# Sheet1.net
KiCad netlist of a schematic drawn in Altium Designer
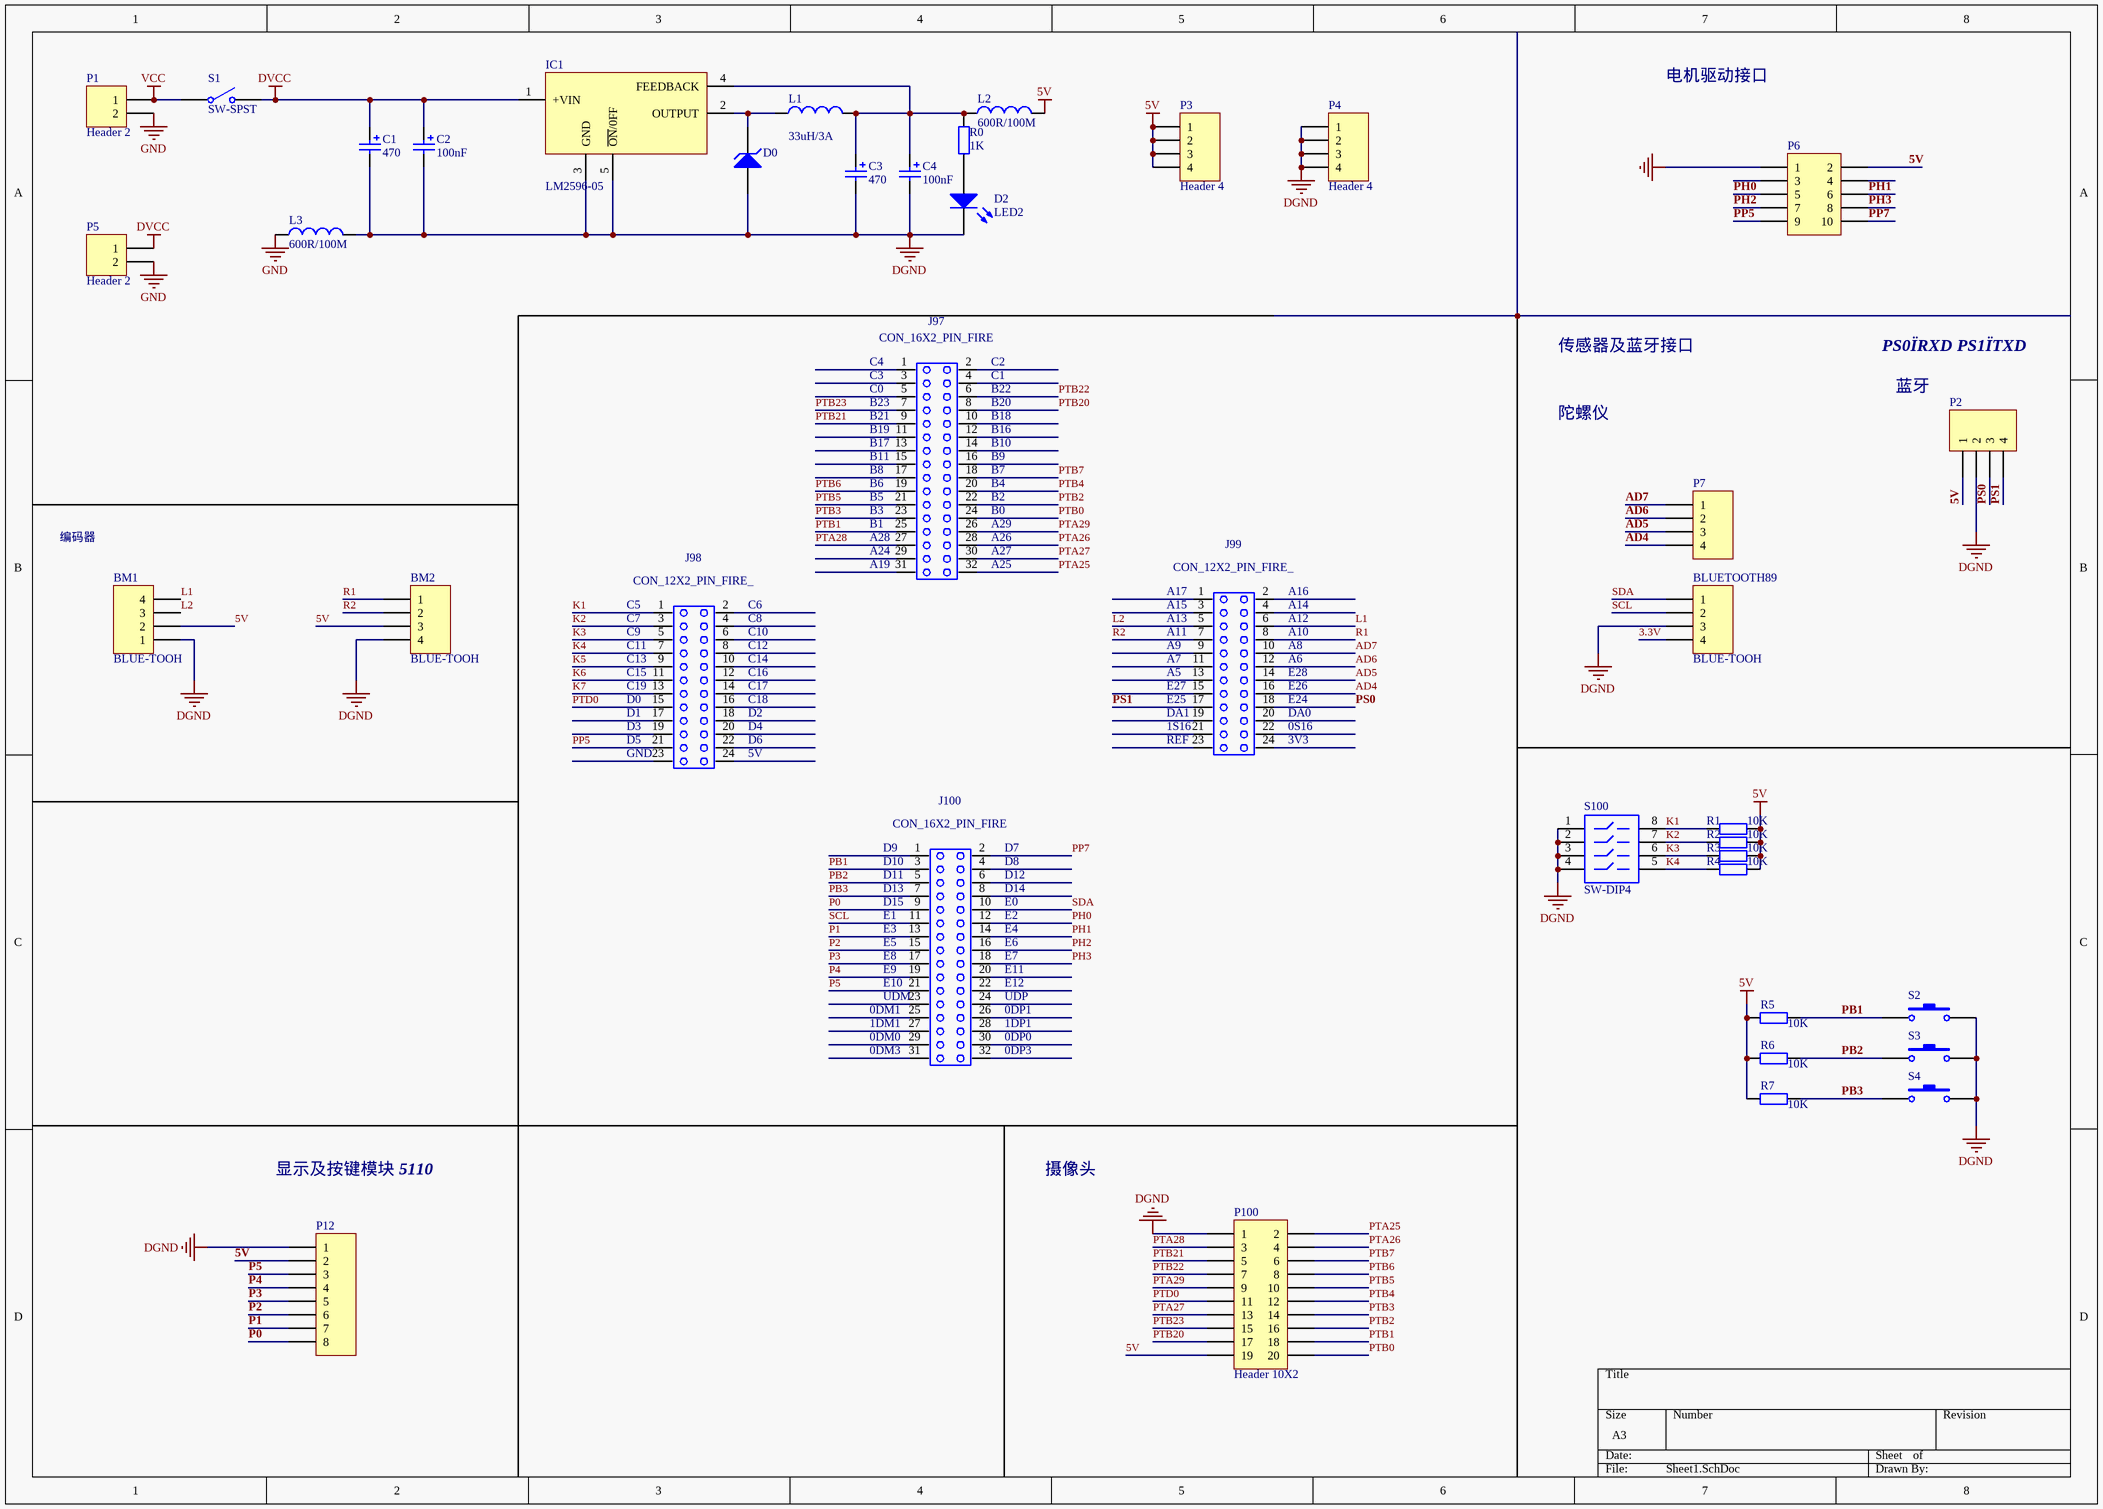
[diagram p0: Sheet1.SchDoc]

(export (version "E")
  (design (tool "Eeschema 10.0.6"))
  (components
    (comp (ref "BLUETOOTH89")
      (value "BLUE-TOOH")
      (footprint "HDR1X4")
      (description "Header, 4-Pin")
      (fields (field (name "PUBLISHER") "Altium Limited"))
      (libsource (lib "Miscellaneous Connectors") (part "Header 4"))
    )
    (comp (ref "BM1")
      (value "BLUE-TOOH")
      (footprint "HDR1X4")
      (description "Header, 4-Pin")
      (fields (field (name "PUBLISHER") "Altium Limited"))
      (libsource (lib "") (part "Header 4_2"))
    )
    (comp (ref "BM2")
      (value "BLUE-TOOH")
      (footprint "HDR1X4")
      (description "Header, 4-Pin")
      (fields (field (name "PUBLISHER") "Altium Limited"))
      (libsource (lib "Miscellaneous Connectors") (part "Header 4"))
    )
    (comp (ref "C1")
      (value "470")
      (footprint "ccc")
      (description "Polarized Capacitor (Axial)")
      (fields (field (name "PUBLISHER") "Altium Limited"))
      (libsource (lib "Miscellaneous Devices") (part "Cap Pol2"))
    )
    (comp (ref "C2")
      (value "100nF")
      (footprint "C0805")
      (description "Polarized Capacitor (Axial)")
      (fields (field (name "PUBLISHER") "Altium Limited"))
      (libsource (lib "Miscellaneous Devices") (part "Cap Pol2"))
    )
    (comp (ref "C3")
      (value "470")
      (footprint "ccc")
      (description "Polarized Capacitor (Axial)")
      (fields (field (name "PUBLISHER") "Altium Limited"))
      (libsource (lib "Miscellaneous Devices") (part "Cap Pol2"))
    )
    (comp (ref "C4")
      (value "100nF")
      (footprint "C0805")
      (description "Polarized Capacitor (Axial)")
      (fields (field (name "PUBLISHER") "Altium Limited"))
      (libsource (lib "Miscellaneous Devices") (part "Cap Pol2"))
    )
    (comp (ref "D0")
      (value "D Zener")
      (footprint "D1810")
      (description "Zener Diode")
      (fields (field (name "PUBLISHER") "Altium Limited"))
      (libsource (lib "Miscellaneous Devices") (part "D Zener"))
    )
    (comp (ref "D2")
      (value "LED2")
      (footprint "D0805")
      (description "Typical RED, GREEN, YELLOW, AMBER GaAs LED")
      (fields (field (name "PUBLISHER") "Altium Limited"))
      (libsource (lib "Miscellaneous Devices") (part "LED2"))
    )
    (comp (ref "IC1")
      (value "LM2596-05")
      (footprint "TO-263-5")
      (libsource (lib "飞思卡尔元件库") (part "LM2596-05"))
    )
    (comp (ref "J97")
      (value "CON_16X2_PIN_FIRE")
      (footprint "CON-16X2-2.54")
      (description "16X2,pin,2.54mm")
      (libsource (lib "*") (part "CON_16X2_PIN_FIRE"))
    )
    (comp (ref "J98")
      (value "CON_12X2_PIN_FIRE_")
      (footprint "CON-12X2-2.54")
      (description "12X2,pin,2.54mm")
      (libsource (lib "*") (part "CON_12X2_PIN_FIRE_"))
    )
    (comp (ref "J99")
      (value "CON_12X2_PIN_FIRE_")
      (footprint "CON-12X2-2.54")
      (description "12X2,pin,2.54mm")
      (libsource (lib "*") (part "CON_12X2_PIN_FIRE_"))
    )
    (comp (ref "J100")
      (value "CON_16X2_PIN_FIRE")
      (footprint "CON-16X2-2.54")
      (description "16X2,pin,2.54mm")
      (libsource (lib "*") (part "CON_16X2_PIN_FIRE"))
    )
    (comp (ref "L1")
      (value "33uH/3A")
      (footprint "L-12*12MM-S")
      (description "Inductor")
      (fields (field (name "PUBLISHER") "Altium Limited"))
      (libsource (lib "Miscellaneous Devices") (part "Inductor"))
    )
    (comp (ref "L2")
      (value "600R/100M")
      (footprint "L1206")
      (description "Inductor")
      (fields (field (name "PUBLISHER") "Altium Limited"))
      (libsource (lib "Miscellaneous Devices") (part "Inductor"))
    )
    (comp (ref "L3")
      (value "600R/100M")
      (footprint "L1206")
      (description "Inductor")
      (fields (field (name "PUBLISHER") "Altium Limited"))
      (libsource (lib "Miscellaneous Devices") (part "Inductor"))
    )
    (comp (ref "P1")
      (value "Header 2")
      (footprint "SIP2-1")
      (description "Header, 2-Pin")
      (fields (field (name "PUBLISHER") "Altium Limited"))
      (libsource (lib "Miscellaneous Connectors") (part "Header 2"))
    )
    (comp (ref "P2")
      (value "Header 4")
      (footprint "HDR1X4")
      (description "Header, 4-Pin")
      (fields (field (name "PUBLISHER") "Altium Limited"))
      (libsource (lib "") (part "Header 4_1"))
    )
    (comp (ref "P3")
      (value "Header 4")
      (footprint "HDR1X4")
      (description "Header, 4-Pin")
      (fields (field (name "PUBLISHER") "Altium Limited"))
      (libsource (lib "Miscellaneous Connectors") (part "Header 4"))
    )
    (comp (ref "P4")
      (value "Header 4")
      (footprint "HDR1X4")
      (description "Header, 4-Pin")
      (fields (field (name "PUBLISHER") "Altium Limited"))
      (libsource (lib "Miscellaneous Connectors") (part "Header 4"))
    )
    (comp (ref "P5")
      (value "Header 2")
      (footprint "SIP2-1")
      (description "Header, 2-Pin")
      (fields (field (name "PUBLISHER") "Altium Limited"))
      (libsource (lib "Miscellaneous Connectors") (part "Header 2"))
    )
    (comp (ref "P6")
      (value "Header 5X2")
      (footprint "HDR2X5")
      (description "Header, 5-Pin, Dual row")
      (fields (field (name "PUBLISHER") "Altium Limited"))
      (libsource (lib "Miscellaneous Connectors") (part "Header 5X2"))
    )
    (comp (ref "P7")
      (value "Header 4")
      (footprint "HDR1X4")
      (description "Header, 4-Pin")
      (fields (field (name "PUBLISHER") "Altium Limited"))
      (libsource (lib "Miscellaneous Connectors") (part "Header 4"))
    )
    (comp (ref "P12")
      (value "Header 8")
      (footprint "HDR1X8")
      (description "Header, 8-Pin")
      (fields (field (name "PUBLISHER") "Altium Limited"))
      (libsource (lib "Miscellaneous Connectors") (part "Header 8"))
    )
    (comp (ref "P100")
      (value "Header 10X2")
      (footprint "HDR2X10")
      (description "Header, 10-Pin, Dual row")
      (fields (field (name "PUBLISHER") "Altium Limited"))
      (libsource (lib "Miscellaneous Connectors") (part "Header 10X2"))
    )
    (comp (ref "R0")
      (value "1K")
      (footprint "R0805")
      (description "Resistor")
      (fields (field (name "Comment") "Res2") (field (name "PUBLISHER") "Altium Limited"))
      (libsource (lib "") (part "Res2_1"))
    )
    (comp (ref "R1")
      (value "10K")
      (footprint "AXIAL-0.4")
      (description "Resistor")
      (fields (field (name "Comment") "Res2") (field (name "PUBLISHER") "Altium Limited"))
      (libsource (lib "Miscellaneous Devices") (part "Res2"))
    )
    (comp (ref "R2")
      (value "10K")
      (footprint "AXIAL-0.4")
      (description "Resistor")
      (fields (field (name "Comment") "Res2") (field (name "PUBLISHER") "Altium Limited"))
      (libsource (lib "Miscellaneous Devices") (part "Res2"))
    )
    (comp (ref "R3")
      (value "10K")
      (footprint "AXIAL-0.4")
      (description "Resistor")
      (fields (field (name "Comment") "Res2") (field (name "PUBLISHER") "Altium Limited"))
      (libsource (lib "Miscellaneous Devices") (part "Res2"))
    )
    (comp (ref "R4")
      (value "10K")
      (footprint "AXIAL-0.4")
      (description "Resistor")
      (fields (field (name "Comment") "Res2") (field (name "PUBLISHER") "Altium Limited"))
      (libsource (lib "Miscellaneous Devices") (part "Res2"))
    )
    (comp (ref "R5")
      (value "10K")
      (footprint "AXIAL-0.4")
      (description "Resistor")
      (fields (field (name "Comment") "Res2") (field (name "PUBLISHER") "Altium Limited"))
      (libsource (lib "Miscellaneous Devices") (part "Res2"))
    )
    (comp (ref "R6")
      (value "10K")
      (footprint "AXIAL-0.4")
      (description "Resistor")
      (fields (field (name "Comment") "Res2") (field (name "PUBLISHER") "Altium Limited"))
      (libsource (lib "Miscellaneous Devices") (part "Res2"))
    )
    (comp (ref "R7")
      (value "10K")
      (footprint "AXIAL-0.4")
      (description "Resistor")
      (fields (field (name "Comment") "Res2") (field (name "PUBLISHER") "Altium Limited"))
      (libsource (lib "Miscellaneous Devices") (part "Res2"))
    )
    (comp (ref "S1")
      (value "SW-SPST")
      (footprint "PCBComponent_1")
      (description "Single-Pole, Single-Throw Switch")
      (fields (field (name "PUBLISHER") "Altium Limited"))
      (libsource (lib "Miscellaneous Devices") (part "SW-SPST"))
    )
    (comp (ref "S2")
      (value "SW-PB")
      (footprint "白色按键")
      (description "Switch")
      (fields (field (name "PUBLISHER") "Altium Limited"))
      (libsource (lib "Miscellaneous Devices") (part "SW-PB"))
    )
    (comp (ref "S3")
      (value "SW-PB")
      (footprint "白色按键")
      (description "Switch")
      (fields (field (name "PUBLISHER") "Altium Limited"))
      (libsource (lib "Miscellaneous Devices") (part "SW-PB"))
    )
    (comp (ref "S4")
      (value "SW-PB")
      (footprint "白色按键")
      (description "Switch")
      (fields (field (name "PUBLISHER") "Altium Limited"))
      (libsource (lib "Miscellaneous Devices") (part "SW-PB"))
    )
    (comp (ref "S100")
      (value "SW-DIP4")
      (footprint "DIP-8")
      (description "DIP Switch")
      (fields (field (name "PUBLISHER") "Altium Limited"))
      (libsource (lib "Miscellaneous Devices") (part "SW-DIP4"))
    )
  )
  (nets
    (net (code "1") (name "/3.3V") (class "Default")
      (node (ref "BLUETOOTH89") (pin "4") (pinfunction "4_4") (pintype "passive"))
    )
    (net (code "2") (name "/AD4") (class "Default")
      (node (ref "J99") (pin "16") (pintype "passive"))
      (node (ref "P7") (pin "4") (pinfunction "4_4") (pintype "passive"))
    )
    (net (code "3") (name "/AD5") (class "Default")
      (node (ref "J99") (pin "14") (pintype "passive"))
      (node (ref "P7") (pin "3") (pinfunction "3_3") (pintype "passive"))
    )
    (net (code "4") (name "/AD6") (class "Default")
      (node (ref "J99") (pin "12") (pintype "passive"))
      (node (ref "P7") (pin "2") (pinfunction "2_2") (pintype "passive"))
    )
    (net (code "5") (name "/AD7") (class "Default")
      (node (ref "J99") (pin "10") (pintype "passive"))
      (node (ref "P7") (pin "1") (pinfunction "1_1") (pintype "passive"))
    )
    (net (code "6") (name "/K1") (class "Default")
      (node (ref "J98") (pin "1") (pintype "passive"))
      (node (ref "R1") (pin "1") (pinfunction "1_1") (pintype "passive"))
      (node (ref "S100") (pin "8") (pinfunction "8_8") (pintype "passive"))
    )
    (net (code "7") (name "/K2") (class "Default")
      (node (ref "J98") (pin "3") (pintype "passive"))
      (node (ref "R2") (pin "1") (pinfunction "1_1") (pintype "passive"))
      (node (ref "S100") (pin "7") (pinfunction "7_7") (pintype "passive"))
    )
    (net (code "8") (name "/K3") (class "Default")
      (node (ref "J98") (pin "5") (pintype "passive"))
      (node (ref "R3") (pin "1") (pinfunction "1_1") (pintype "passive"))
      (node (ref "S100") (pin "6") (pinfunction "6_6") (pintype "passive"))
    )
    (net (code "9") (name "/K4") (class "Default")
      (node (ref "J98") (pin "7") (pintype "passive"))
      (node (ref "R4") (pin "1") (pinfunction "1_1") (pintype "passive"))
      (node (ref "S100") (pin "5") (pinfunction "5_5") (pintype "passive"))
    )
    (net (code "10") (name "/K5") (class "Default") (node (ref "J98") (pin "9") (pintype "passive")))
    (net (code "11") (name "/K6") (class "Default") (node (ref "J98") (pin "11") (pintype "passive")))
    (net (code "12") (name "/K7") (class "Default") (node (ref "J98") (pin "13") (pintype "passive")))
    (net (code "13") (name "/L1") (class "Default")
      (node (ref "BM1") (pin "4") (pinfunction "4_4") (pintype "passive"))
      (node (ref "J99") (pin "6") (pintype "passive"))
    )
    (net (code "14") (name "/L2") (class "Default")
      (node (ref "BM1") (pin "3") (pinfunction "3_3") (pintype "passive"))
      (node (ref "J99") (pin "5") (pintype "passive"))
    )
    (net (code "15") (name "/P0") (class "Default")
      (node (ref "J100") (pin "9") (pintype "passive"))
      (node (ref "P12") (pin "8") (pinfunction "8_8") (pintype "passive"))
    )
    (net (code "16") (name "/P1") (class "Default")
      (node (ref "J100") (pin "13") (pintype "passive"))
      (node (ref "P12") (pin "7") (pinfunction "7_7") (pintype "passive"))
    )
    (net (code "17") (name "/P2") (class "Default")
      (node (ref "J100") (pin "15") (pintype "passive"))
      (node (ref "P12") (pin "6") (pinfunction "6_6") (pintype "passive"))
    )
    (net (code "18") (name "/P3") (class "Default")
      (node (ref "J100") (pin "17") (pintype "passive"))
      (node (ref "P12") (pin "5") (pinfunction "5_5") (pintype "passive"))
    )
    (net (code "19") (name "/P4") (class "Default")
      (node (ref "J100") (pin "19") (pintype "passive"))
      (node (ref "P12") (pin "4") (pinfunction "4_4") (pintype "passive"))
    )
    (net (code "20") (name "/P5") (class "Default")
      (node (ref "J100") (pin "21") (pintype "passive"))
      (node (ref "P12") (pin "3") (pinfunction "3_3") (pintype "passive"))
    )
    (net (code "21") (name "/PB1") (class "Default")
      (node (ref "J100") (pin "3") (pintype "passive"))
      (node (ref "R5") (pin "2") (pinfunction "2_2") (pintype "passive"))
      (node (ref "S2") (pin "1") (pinfunction "1_1") (pintype "passive"))
    )
    (net (code "22") (name "/PB2") (class "Default")
      (node (ref "J100") (pin "5") (pintype "passive"))
      (node (ref "R6") (pin "2") (pinfunction "2_2") (pintype "passive"))
      (node (ref "S3") (pin "1") (pinfunction "1_1") (pintype "passive"))
    )
    (net (code "23") (name "/PB3") (class "Default")
      (node (ref "J100") (pin "7") (pintype "passive"))
      (node (ref "R7") (pin "2") (pinfunction "2_2") (pintype "passive"))
      (node (ref "S4") (pin "1") (pinfunction "1_1") (pintype "passive"))
    )
    (net (code "24") (name "/PH0") (class "Default")
      (node (ref "J100") (pin "12") (pintype "passive"))
      (node (ref "P6") (pin "5") (pinfunction "5_5") (pintype "passive"))
    )
    (net (code "25") (name "/PH1") (class "Default")
      (node (ref "J100") (pin "14") (pintype "passive"))
      (node (ref "P6") (pin "6") (pinfunction "6_6") (pintype "passive"))
    )
    (net (code "26") (name "/PH2") (class "Default")
      (node (ref "J100") (pin "16") (pintype "passive"))
      (node (ref "P6") (pin "7") (pinfunction "7_7") (pintype "passive"))
    )
    (net (code "27") (name "/PH3") (class "Default")
      (node (ref "J100") (pin "18") (pintype "passive"))
      (node (ref "P6") (pin "8") (pinfunction "8_8") (pintype "passive"))
    )
    (net (code "28") (name "/PP5") (class "Default")
      (node (ref "J98") (pin "21") (pintype "passive"))
      (node (ref "P6") (pin "9") (pinfunction "9_9") (pintype "passive"))
    )
    (net (code "29") (name "/PP7") (class "Default")
      (node (ref "J100") (pin "2") (pintype "passive"))
      (node (ref "P6") (pin "10") (pinfunction "10_10") (pintype "passive"))
    )
    (net (code "30") (name "/PS0") (class "Default")
      (node (ref "J99") (pin "18") (pintype "passive"))
      (node (ref "P2") (pin "3") (pinfunction "3_3") (pintype "passive"))
    )
    (net (code "31") (name "/PS1") (class "Default")
      (node (ref "J99") (pin "17") (pintype "passive"))
      (node (ref "P2") (pin "4") (pinfunction "4_4") (pintype "passive"))
    )
    (net (code "32") (name "/PTA25") (class "Default")
      (node (ref "J97") (pin "32") (pintype "passive"))
      (node (ref "P100") (pin "2") (pinfunction "2_2") (pintype "passive"))
    )
    (net (code "33") (name "/PTA26") (class "Default")
      (node (ref "J97") (pin "28") (pintype "passive"))
      (node (ref "P100") (pin "4") (pinfunction "4_4") (pintype "passive"))
    )
    (net (code "34") (name "/PTA27") (class "Default")
      (node (ref "J97") (pin "30") (pintype "passive"))
      (node (ref "P100") (pin "13") (pinfunction "13_13") (pintype "passive"))
    )
    (net (code "35") (name "/PTA28") (class "Default")
      (node (ref "J97") (pin "27") (pintype "passive"))
      (node (ref "P100") (pin "3") (pinfunction "3_3") (pintype "passive"))
    )
    (net (code "36") (name "/PTA29") (class "Default")
      (node (ref "J97") (pin "26") (pintype "passive"))
      (node (ref "P100") (pin "9") (pinfunction "9_9") (pintype "passive"))
    )
    (net (code "37") (name "/PTB0") (class "Default")
      (node (ref "J97") (pin "24") (pintype "passive"))
      (node (ref "P100") (pin "20") (pinfunction "20_20") (pintype "passive"))
    )
    (net (code "38") (name "/PTB1") (class "Default")
      (node (ref "J97") (pin "25") (pintype "passive"))
      (node (ref "P100") (pin "18") (pinfunction "18_18") (pintype "passive"))
    )
    (net (code "39") (name "/PTB2") (class "Default")
      (node (ref "J97") (pin "22") (pintype "passive"))
      (node (ref "P100") (pin "16") (pinfunction "16_16") (pintype "passive"))
    )
    (net (code "40") (name "/PTB3") (class "Default")
      (node (ref "J97") (pin "23") (pintype "passive"))
      (node (ref "P100") (pin "14") (pinfunction "14_14") (pintype "passive"))
    )
    (net (code "41") (name "/PTB4") (class "Default")
      (node (ref "J97") (pin "20") (pintype "passive"))
      (node (ref "P100") (pin "12") (pinfunction "12_12") (pintype "passive"))
    )
    (net (code "42") (name "/PTB5") (class "Default")
      (node (ref "J97") (pin "21") (pintype "passive"))
      (node (ref "P100") (pin "10") (pinfunction "10_10") (pintype "passive"))
    )
    (net (code "43") (name "/PTB6") (class "Default")
      (node (ref "J97") (pin "19") (pintype "passive"))
      (node (ref "P100") (pin "8") (pinfunction "8_8") (pintype "passive"))
    )
    (net (code "44") (name "/PTB7") (class "Default")
      (node (ref "J97") (pin "18") (pintype "passive"))
      (node (ref "P100") (pin "6") (pinfunction "6_6") (pintype "passive"))
    )
    (net (code "45") (name "/PTB20") (class "Default")
      (node (ref "J97") (pin "8") (pintype "passive"))
      (node (ref "P100") (pin "17") (pinfunction "17_17") (pintype "passive"))
    )
    (net (code "46") (name "/PTB21") (class "Default")
      (node (ref "J97") (pin "9") (pintype "passive"))
      (node (ref "P100") (pin "5") (pinfunction "5_5") (pintype "passive"))
    )
    (net (code "47") (name "/PTB22") (class "Default")
      (node (ref "J97") (pin "6") (pintype "passive"))
      (node (ref "P100") (pin "7") (pinfunction "7_7") (pintype "passive"))
    )
    (net (code "48") (name "/PTB23") (class "Default")
      (node (ref "J97") (pin "7") (pintype "passive"))
      (node (ref "P100") (pin "15") (pinfunction "15_15") (pintype "passive"))
    )
    (net (code "49") (name "/PTD0") (class "Default")
      (node (ref "J98") (pin "15") (pintype "passive"))
      (node (ref "P100") (pin "11") (pinfunction "11_11") (pintype "passive"))
    )
    (net (code "50") (name "/R1") (class "Default")
      (node (ref "BM2") (pin "1") (pinfunction "1_1") (pintype "passive"))
      (node (ref "J99") (pin "8") (pintype "passive"))
    )
    (net (code "51") (name "/R2") (class "Default")
      (node (ref "BM2") (pin "2") (pinfunction "2_2") (pintype "passive"))
      (node (ref "J99") (pin "7") (pintype "passive"))
    )
    (net (code "52") (name "/SCL") (class "Default")
      (node (ref "BLUETOOTH89") (pin "2") (pinfunction "2_2") (pintype "passive"))
      (node (ref "J100") (pin "11") (pintype "passive"))
    )
    (net (code "53") (name "/SDA") (class "Default")
      (node (ref "BLUETOOTH89") (pin "1") (pinfunction "1_1") (pintype "passive"))
      (node (ref "J100") (pin "10") (pintype "passive"))
    )
    (net (code "54") (name "5V") (class "Default")
      (node (ref "BM1") (pin "2") (pinfunction "2_2") (pintype "passive"))
      (node (ref "BM2") (pin "3") (pinfunction "3_3") (pintype "passive"))
      (node (ref "L2") (pin "2") (pinfunction "2_2") (pintype "passive"))
      (node (ref "P100") (pin "19") (pinfunction "19_19") (pintype "passive"))
      (node (ref "P12") (pin "2") (pinfunction "2_2") (pintype "passive"))
      (node (ref "P2") (pin "1") (pinfunction "1_1") (pintype "passive"))
      (node (ref "P3") (pin "1") (pinfunction "1_1") (pintype "passive"))
      (node (ref "P3") (pin "2") (pinfunction "2_2") (pintype "passive"))
      (node (ref "P3") (pin "3") (pinfunction "3_3") (pintype "passive"))
      (node (ref "P3") (pin "4") (pinfunction "4_4") (pintype "passive"))
      (node (ref "P6") (pin "2") (pinfunction "2_2") (pintype "passive"))
      (node (ref "R1") (pin "2") (pinfunction "2_2") (pintype "passive"))
      (node (ref "R2") (pin "2") (pinfunction "2_2") (pintype "passive"))
      (node (ref "R3") (pin "2") (pinfunction "2_2") (pintype "passive"))
      (node (ref "R4") (pin "2") (pinfunction "2_2") (pintype "passive"))
      (node (ref "R5") (pin "1") (pinfunction "1_1") (pintype "passive"))
      (node (ref "R6") (pin "1") (pinfunction "1_1") (pintype "passive"))
      (node (ref "R7") (pin "1") (pinfunction "1_1") (pintype "passive"))
    )
    (net (code "55") (name "DGND") (class "Default")
      (node (ref "BLUETOOTH89") (pin "3") (pinfunction "3_3") (pintype "passive"))
      (node (ref "BM1") (pin "1") (pinfunction "1_1") (pintype "passive"))
      (node (ref "BM2") (pin "4") (pinfunction "4_4") (pintype "passive"))
      (node (ref "C1") (pin "2") (pinfunction "2_2") (pintype "passive"))
      (node (ref "C2") (pin "2") (pinfunction "2_2") (pintype "passive"))
      (node (ref "C3") (pin "2") (pinfunction "2_2") (pintype "passive"))
      (node (ref "C4") (pin "2") (pinfunction "2_2") (pintype "passive"))
      (node (ref "D0") (pin "1") (pinfunction "A_1") (pintype "passive"))
      (node (ref "D2") (pin "2") (pinfunction "K_2") (pintype "passive"))
      (node (ref "IC1") (pin "3") (pinfunction "GND_3") (pintype "passive"))
      (node (ref "IC1") (pin "5") (pinfunction "~{ON}/0FF_5") (pintype "passive"))
      (node (ref "L3") (pin "2") (pinfunction "2_2") (pintype "passive"))
      (node (ref "P100") (pin "1") (pinfunction "1_1") (pintype "passive"))
      (node (ref "P12") (pin "1") (pinfunction "1_1") (pintype "passive"))
      (node (ref "P2") (pin "2") (pinfunction "2_2") (pintype "passive"))
      (node (ref "P4") (pin "1") (pinfunction "1_1") (pintype "passive"))
      (node (ref "P4") (pin "2") (pinfunction "2_2") (pintype "passive"))
      (node (ref "P4") (pin "3") (pinfunction "3_3") (pintype "passive"))
      (node (ref "P4") (pin "4") (pinfunction "4_4") (pintype "passive"))
      (node (ref "S100") (pin "1") (pinfunction "1_1") (pintype "passive"))
      (node (ref "S100") (pin "2") (pinfunction "2_2") (pintype "passive"))
      (node (ref "S100") (pin "3") (pinfunction "3_3") (pintype "passive"))
      (node (ref "S100") (pin "4") (pinfunction "4_4") (pintype "passive"))
      (node (ref "S2") (pin "2") (pinfunction "2_2") (pintype "passive"))
      (node (ref "S3") (pin "2") (pinfunction "2_2") (pintype "passive"))
      (node (ref "S4") (pin "2") (pinfunction "2_2") (pintype "passive"))
    )
    (net (code "56") (name "DVCC") (class "Default")
      (node (ref "C1") (pin "1") (pinfunction "1_1") (pintype "passive"))
      (node (ref "C2") (pin "1") (pinfunction "1_1") (pintype "passive"))
      (node (ref "IC1") (pin "1") (pinfunction "+VIN_1") (pintype "passive"))
      (node (ref "P5") (pin "1") (pinfunction "1_1") (pintype "passive"))
      (node (ref "S1") (pin "2") (pinfunction "NO_2") (pintype "passive"))
    )
    (net (code "57") (name "GND") (class "Default")
      (node (ref "L3") (pin "1") (pinfunction "1_1") (pintype "passive"))
      (node (ref "P1") (pin "2") (pinfunction "2_2") (pintype "passive"))
      (node (ref "P5") (pin "2") (pinfunction "2_2") (pintype "passive"))
      (node (ref "P6") (pin "1") (pinfunction "1_1") (pintype "passive"))
    )
    (net (code "58") (name "Net-(D0-K)") (class "Default")
      (node (ref "D0") (pin "2") (pinfunction "K_2") (pintype "passive"))
      (node (ref "IC1") (pin "2") (pinfunction "OUTPUT_2") (pintype "passive"))
      (node (ref "L1") (pin "1") (pinfunction "1_1") (pintype "passive"))
    )
    (net (code "59") (name "Net-(D2-A)") (class "Default")
      (node (ref "D2") (pin "1") (pinfunction "A_1") (pintype "passive"))
      (node (ref "R0") (pin "2") (pinfunction "2_2") (pintype "passive"))
    )
    (net (code "60") (name "Net-(IC1-FEEDBACK)") (class "Default")
      (node (ref "C3") (pin "1") (pinfunction "1_1") (pintype "passive"))
      (node (ref "C4") (pin "1") (pinfunction "1_1") (pintype "passive"))
      (node (ref "IC1") (pin "4") (pinfunction "FEEDBACK_4") (pintype "passive"))
      (node (ref "L1") (pin "2") (pinfunction "2_2") (pintype "passive"))
      (node (ref "L2") (pin "1") (pinfunction "1_1") (pintype "passive"))
      (node (ref "R0") (pin "1") (pinfunction "1_1") (pintype "passive"))
    )
    (net (code "61") (name "VCC") (class "Default")
      (node (ref "P1") (pin "1") (pinfunction "1_1") (pintype "passive"))
      (node (ref "S1") (pin "1") (pinfunction "COMMON_1") (pintype "passive"))
    )
    (net (code "62") (name "unconnected-(J97-Pad1)") (class "Default")
      (node (ref "J97") (pin "1") (pintype "passive"))
    )
    (net (code "63") (name "unconnected-(J97-Pad2)") (class "Default")
      (node (ref "J97") (pin "2") (pintype "passive"))
    )
    (net (code "64") (name "unconnected-(J97-Pad3)") (class "Default")
      (node (ref "J97") (pin "3") (pintype "passive"))
    )
    (net (code "65") (name "unconnected-(J97-Pad4)") (class "Default")
      (node (ref "J97") (pin "4") (pintype "passive"))
    )
    (net (code "66") (name "unconnected-(J97-Pad5)") (class "Default")
      (node (ref "J97") (pin "5") (pintype "passive"))
    )
    (net (code "67") (name "unconnected-(J97-Pad10)") (class "Default")
      (node (ref "J97") (pin "10") (pintype "passive"))
    )
    (net (code "68") (name "unconnected-(J97-Pad11)") (class "Default")
      (node (ref "J97") (pin "11") (pintype "passive"))
    )
    (net (code "69") (name "unconnected-(J97-Pad12)") (class "Default")
      (node (ref "J97") (pin "12") (pintype "passive"))
    )
    (net (code "70") (name "unconnected-(J97-Pad13)") (class "Default")
      (node (ref "J97") (pin "13") (pintype "passive"))
    )
    (net (code "71") (name "unconnected-(J97-Pad14)") (class "Default")
      (node (ref "J97") (pin "14") (pintype "passive"))
    )
    (net (code "72") (name "unconnected-(J97-Pad15)") (class "Default")
      (node (ref "J97") (pin "15") (pintype "passive"))
    )
    (net (code "73") (name "unconnected-(J97-Pad16)") (class "Default")
      (node (ref "J97") (pin "16") (pintype "passive"))
    )
    (net (code "74") (name "unconnected-(J97-Pad17)") (class "Default")
      (node (ref "J97") (pin "17") (pintype "passive"))
    )
    (net (code "75") (name "unconnected-(J97-Pad29)") (class "Default")
      (node (ref "J97") (pin "29") (pintype "passive"))
    )
    (net (code "76") (name "unconnected-(J97-Pad31)") (class "Default")
      (node (ref "J97") (pin "31") (pintype "passive"))
    )
    (net (code "77") (name "unconnected-(J98-Pad2)") (class "Default")
      (node (ref "J98") (pin "2") (pintype "passive"))
    )
    (net (code "78") (name "unconnected-(J98-Pad4)") (class "Default")
      (node (ref "J98") (pin "4") (pintype "passive"))
    )
    (net (code "79") (name "unconnected-(J98-Pad6)") (class "Default")
      (node (ref "J98") (pin "6") (pintype "passive"))
    )
    (net (code "80") (name "unconnected-(J98-Pad8)") (class "Default")
      (node (ref "J98") (pin "8") (pintype "passive"))
    )
    (net (code "81") (name "unconnected-(J98-Pad10)") (class "Default")
      (node (ref "J98") (pin "10") (pintype "passive"))
    )
    (net (code "82") (name "unconnected-(J98-Pad12)") (class "Default")
      (node (ref "J98") (pin "12") (pintype "passive"))
    )
    (net (code "83") (name "unconnected-(J98-Pad14)") (class "Default")
      (node (ref "J98") (pin "14") (pintype "passive"))
    )
    (net (code "84") (name "unconnected-(J98-Pad16)") (class "Default")
      (node (ref "J98") (pin "16") (pintype "passive"))
    )
    (net (code "85") (name "unconnected-(J98-Pad17)") (class "Default")
      (node (ref "J98") (pin "17") (pintype "passive"))
    )
    (net (code "86") (name "unconnected-(J98-Pad18)") (class "Default")
      (node (ref "J98") (pin "18") (pintype "passive"))
    )
    (net (code "87") (name "unconnected-(J98-Pad19)") (class "Default")
      (node (ref "J98") (pin "19") (pintype "passive"))
    )
    (net (code "88") (name "unconnected-(J98-Pad20)") (class "Default")
      (node (ref "J98") (pin "20") (pintype "passive"))
    )
    (net (code "89") (name "unconnected-(J98-Pad22)") (class "Default")
      (node (ref "J98") (pin "22") (pintype "passive"))
    )
    (net (code "90") (name "unconnected-(J98-Pad23)") (class "Default")
      (node (ref "J98") (pin "23") (pintype "passive"))
    )
    (net (code "91") (name "unconnected-(J98-Pad24)") (class "Default")
      (node (ref "J98") (pin "24") (pintype "passive"))
    )
    (net (code "92") (name "unconnected-(J99-Pad1)") (class "Default")
      (node (ref "J99") (pin "1") (pintype "passive"))
    )
    (net (code "93") (name "unconnected-(J99-Pad2)") (class "Default")
      (node (ref "J99") (pin "2") (pintype "passive"))
    )
    (net (code "94") (name "unconnected-(J99-Pad3)") (class "Default")
      (node (ref "J99") (pin "3") (pintype "passive"))
    )
    (net (code "95") (name "unconnected-(J99-Pad4)") (class "Default")
      (node (ref "J99") (pin "4") (pintype "passive"))
    )
    (net (code "96") (name "unconnected-(J99-Pad9)") (class "Default")
      (node (ref "J99") (pin "9") (pintype "passive"))
    )
    (net (code "97") (name "unconnected-(J99-Pad11)") (class "Default")
      (node (ref "J99") (pin "11") (pintype "passive"))
    )
    (net (code "98") (name "unconnected-(J99-Pad13)") (class "Default")
      (node (ref "J99") (pin "13") (pintype "passive"))
    )
    (net (code "99") (name "unconnected-(J99-Pad15)") (class "Default")
      (node (ref "J99") (pin "15") (pintype "passive"))
    )
    (net (code "100") (name "unconnected-(J99-Pad19)") (class "Default")
      (node (ref "J99") (pin "19") (pintype "passive"))
    )
    (net (code "101") (name "unconnected-(J99-Pad20)") (class "Default")
      (node (ref "J99") (pin "20") (pintype "passive"))
    )
    (net (code "102") (name "unconnected-(J99-Pad21)") (class "Default")
      (node (ref "J99") (pin "21") (pintype "passive"))
    )
    (net (code "103") (name "unconnected-(J99-Pad22)") (class "Default")
      (node (ref "J99") (pin "22") (pintype "passive"))
    )
    (net (code "104") (name "unconnected-(J99-Pad23)") (class "Default")
      (node (ref "J99") (pin "23") (pintype "passive"))
    )
    (net (code "105") (name "unconnected-(J99-Pad24)") (class "Default")
      (node (ref "J99") (pin "24") (pintype "passive"))
    )
    (net (code "106") (name "unconnected-(J100-Pad1)") (class "Default")
      (node (ref "J100") (pin "1") (pintype "passive"))
    )
    (net (code "107") (name "unconnected-(J100-Pad4)") (class "Default")
      (node (ref "J100") (pin "4") (pintype "passive"))
    )
    (net (code "108") (name "unconnected-(J100-Pad6)") (class "Default")
      (node (ref "J100") (pin "6") (pintype "passive"))
    )
    (net (code "109") (name "unconnected-(J100-Pad8)") (class "Default")
      (node (ref "J100") (pin "8") (pintype "passive"))
    )
    (net (code "110") (name "unconnected-(J100-Pad20)") (class "Default")
      (node (ref "J100") (pin "20") (pintype "passive"))
    )
    (net (code "111") (name "unconnected-(J100-Pad22)") (class "Default")
      (node (ref "J100") (pin "22") (pintype "passive"))
    )
    (net (code "112") (name "unconnected-(J100-Pad23)") (class "Default")
      (node (ref "J100") (pin "23") (pintype "passive"))
    )
    (net (code "113") (name "unconnected-(J100-Pad24)") (class "Default")
      (node (ref "J100") (pin "24") (pintype "passive"))
    )
    (net (code "114") (name "unconnected-(J100-Pad25)") (class "Default")
      (node (ref "J100") (pin "25") (pintype "passive"))
    )
    (net (code "115") (name "unconnected-(J100-Pad26)") (class "Default")
      (node (ref "J100") (pin "26") (pintype "passive"))
    )
    (net (code "116") (name "unconnected-(J100-Pad27)") (class "Default")
      (node (ref "J100") (pin "27") (pintype "passive"))
    )
    (net (code "117") (name "unconnected-(J100-Pad28)") (class "Default")
      (node (ref "J100") (pin "28") (pintype "passive"))
    )
    (net (code "118") (name "unconnected-(J100-Pad29)") (class "Default")
      (node (ref "J100") (pin "29") (pintype "passive"))
    )
    (net (code "119") (name "unconnected-(J100-Pad30)") (class "Default")
      (node (ref "J100") (pin "30") (pintype "passive"))
    )
    (net (code "120") (name "unconnected-(J100-Pad31)") (class "Default")
      (node (ref "J100") (pin "31") (pintype "passive"))
    )
    (net (code "121") (name "unconnected-(J100-Pad32)") (class "Default")
      (node (ref "J100") (pin "32") (pintype "passive"))
    )
    (net (code "122") (name "unconnected-(P6-Pad3)") (class "Default")
      (node (ref "P6") (pin "3") (pinfunction "3_3") (pintype "passive"))
    )
    (net (code "123") (name "unconnected-(P6-Pad4)") (class "Default")
      (node (ref "P6") (pin "4") (pinfunction "4_4") (pintype "passive"))
    )
  )
)
